# core.net
KiCad netlist of a schematic drawn in Altium Designer
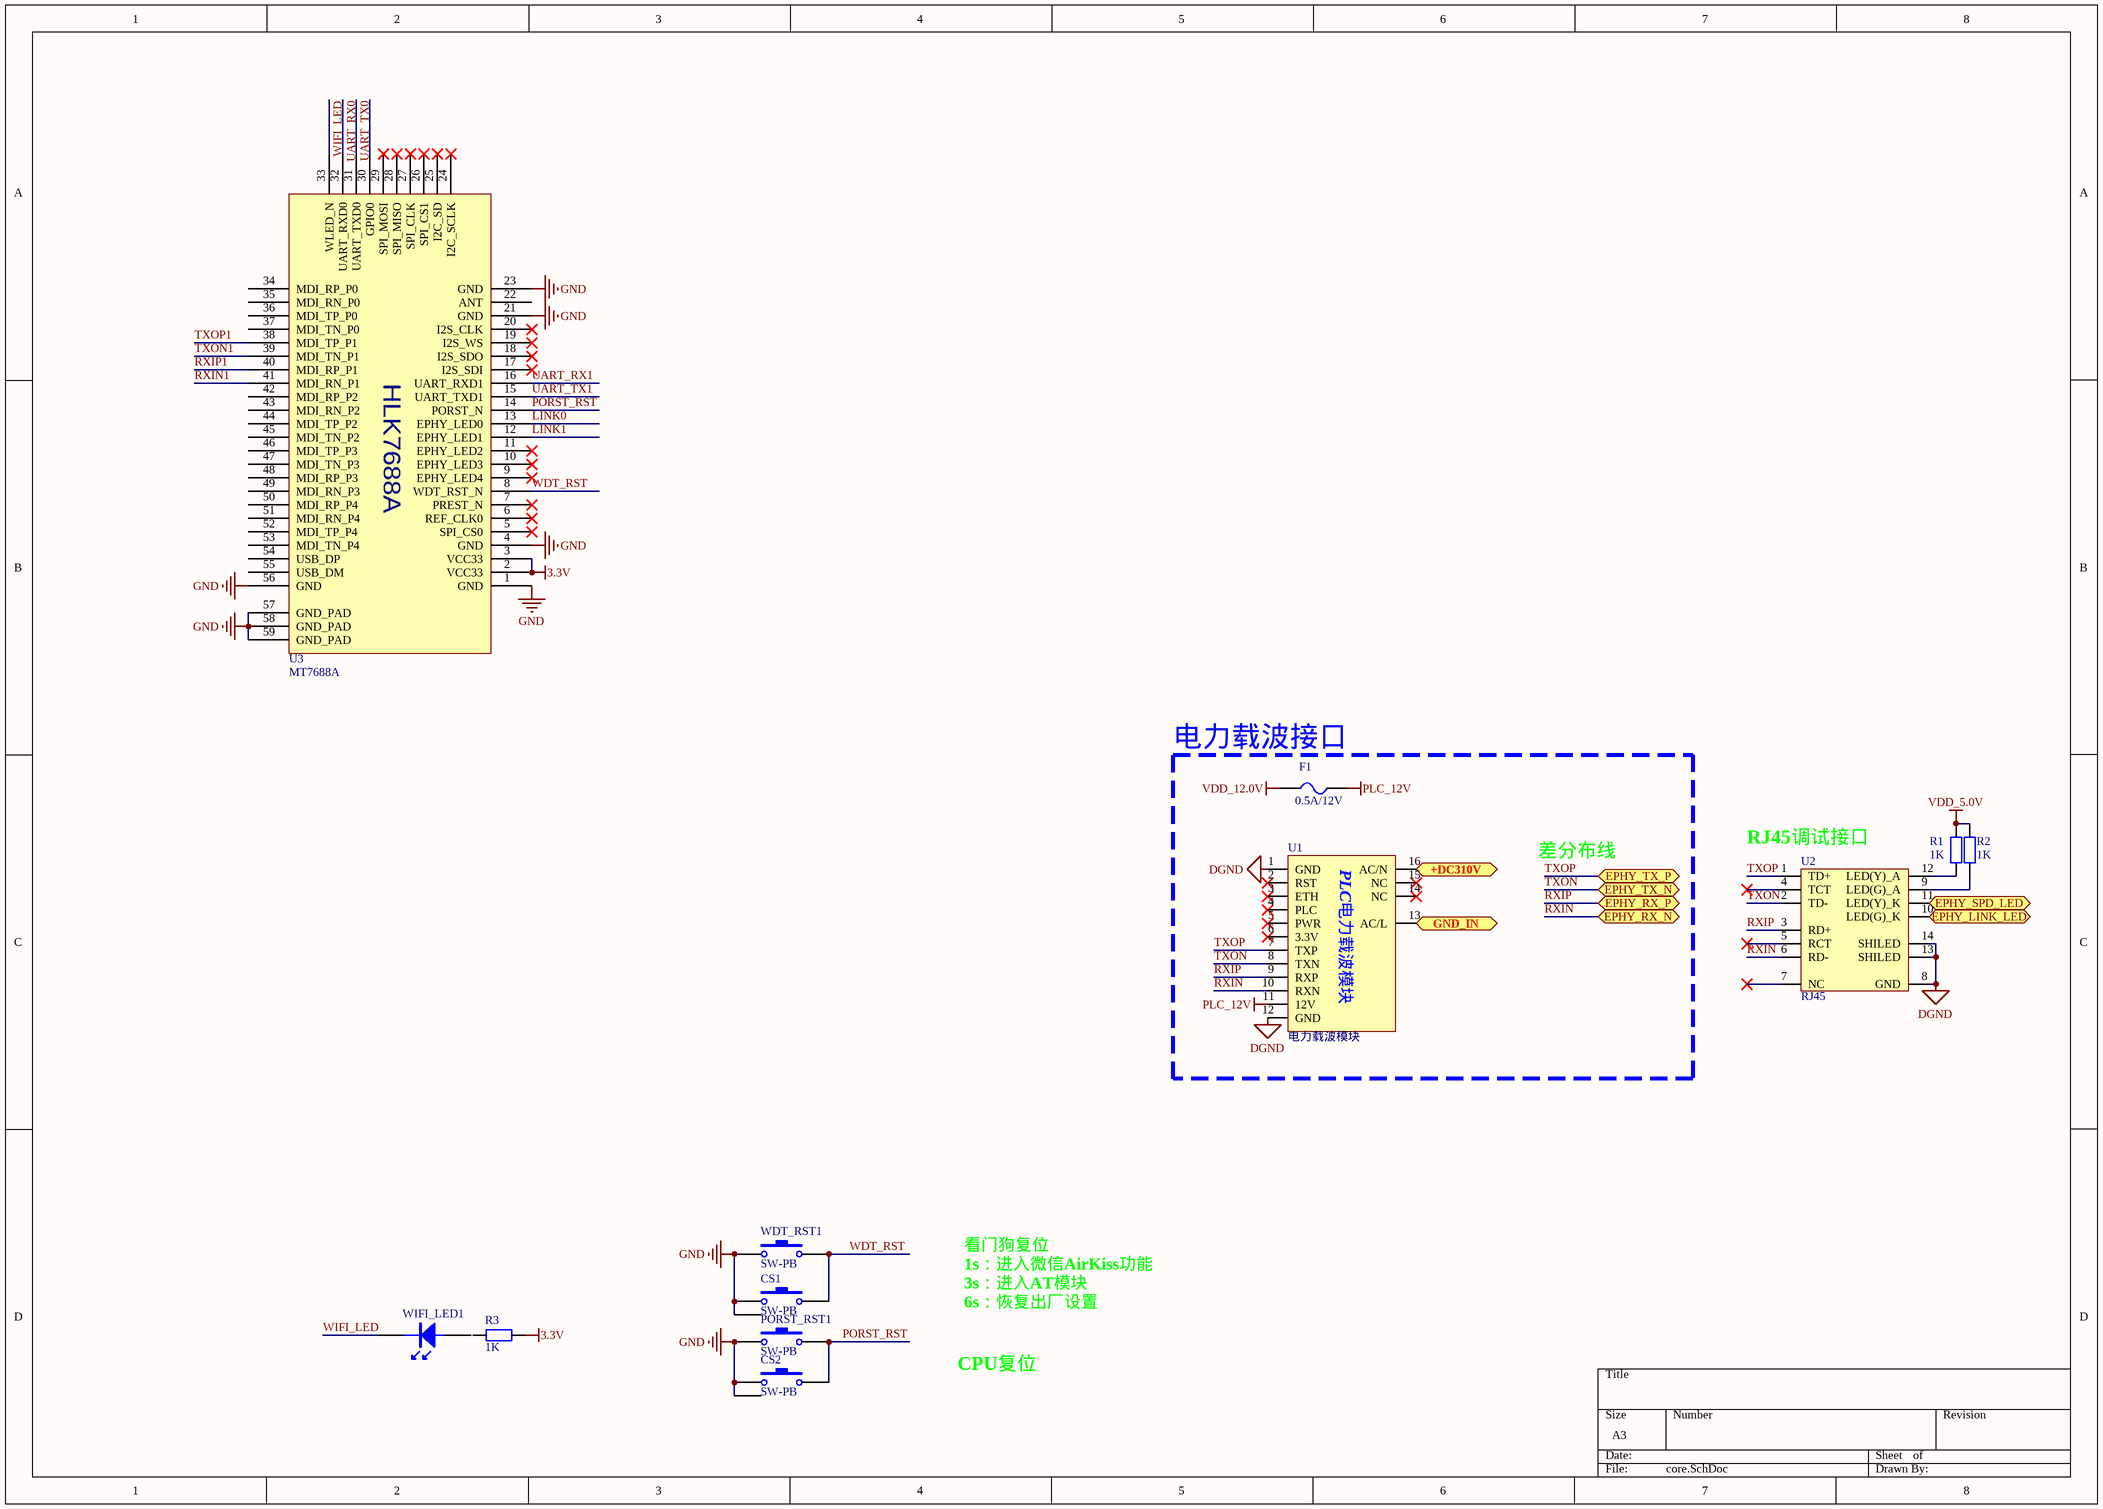
[diagram p0: core.SchDoc]

(export (version "E")
  (design (tool "Eeschema 10.0.6"))
  (components
    (comp (ref "CS1")
      (value "SW-PB")
      (footprint "K5")
      (description "Switch")
      (fields (field (name "PUBLISHER") "Altium Limited"))
      (libsource (lib "Miscellaneous Devices") (part "SW-PB"))
    )
    (comp (ref "CS2")
      (value "SW-PB")
      (footprint "K5")
      (description "Switch")
      (fields (field (name "PUBLISHER") "Altium Limited"))
      (libsource (lib "Miscellaneous Devices") (part "SW-PB"))
    )
    (comp (ref "F1")
      (value "0.5A/12V")
      (footprint "1206F")
      (description "保险丝")
      (libsource (lib "集大电协1.5") (part "Fuse"))
    )
    (comp (ref "PORST_RST1")
      (value "SW-PB")
      (footprint "SWITCH")
      (description "Switch")
      (fields (field (name "PUBLISHER") "Altium Limited"))
      (libsource (lib "") (part "SW-PB_1"))
    )
    (comp (ref "R1")
      (value "1K")
      (footprint "0805R")
      (description "电阻")
      (libsource (lib "集大电协1.5") (part "Res"))
    )
    (comp (ref "R2")
      (value "1K")
      (footprint "0805R")
      (description "电阻")
      (libsource (lib "集大电协1.5") (part "Res"))
    )
    (comp (ref "R3")
      (value "1K")
      (footprint "0805R")
      (description "电阻")
      (libsource (lib "Mylib") (part "Res"))
    )
    (comp (ref "U1")
      (value "电力载波模块")
      (footprint "电力载波模块6410（贴片排母）")
      (libsource (lib "集大电协1.5") (part "电力载波模块6410"))
    )
    (comp (ref "U2") (value "RJ45") (footprint "RJ45") (libsource (lib "集大电协1.5") (part "RJ45")))
    (comp (ref "U3")
      (value "MT7688A")
      (footprint "MT7688A")
      (description "MT7688A模组")
      (libsource (lib "Mylib") (part "MT7688A"))
    )
    (comp (ref "WDT_RST1")
      (value "SW-PB")
      (footprint "SWITCH")
      (description "Switch")
      (fields (field (name "PUBLISHER") "Altium Limited"))
      (libsource (lib "") (part "SW-PB_1"))
    )
    (comp (ref "WIFI_LED1")
      (value "~")
      (footprint "0603LED")
      (libsource (lib "Miscellaneous Devices") (part "LED"))
    )
  )
  (nets
    (net (code "1") (name "/+DC310V") (class "Default")
      (node (ref "U1") (pin "16") (pinfunction "AC/N_16") (pintype "passive"))
    )
    (net (code "2") (name "/EPHY_LINK_LED") (class "Default")
      (node (ref "U2") (pin "10") (pinfunction "LED(G)_K_10") (pintype "passive"))
    )
    (net (code "3") (name "/EPHY_SPD_LED") (class "Default")
      (node (ref "U2") (pin "11") (pinfunction "LED(Y)_K_11") (pintype "passive"))
    )
    (net (code "4") (name "/GND_IN") (class "Default")
      (node (ref "U1") (pin "13") (pinfunction "AC/L_13") (pintype "passive"))
    )
    (net (code "5") (name "/LINK0") (class "Default")
      (node (ref "U3") (pin "13") (pinfunction "EPHY_LED0_13") (pintype "passive"))
    )
    (net (code "6") (name "/LINK1") (class "Default")
      (node (ref "U3") (pin "12") (pinfunction "EPHY_LED1_12") (pintype "passive"))
    )
    (net (code "7") (name "/PORST_RST") (class "Default")
      (node (ref "CS2") (pin "2") (pinfunction "2_2") (pintype "passive"))
      (node (ref "PORST_RST1") (pin "2") (pinfunction "2_2") (pintype "passive"))
      (node (ref "U3") (pin "14") (pinfunction "PORST_N_14") (pintype "passive"))
    )
    (net (code "8") (name "/RXIN") (class "Default")
      (node (ref "U1") (pin "10") (pinfunction "RXN_10") (pintype "passive"))
      (node (ref "U2") (pin "6") (pinfunction "RD-_6") (pintype "passive"))
    )
    (net (code "9") (name "/RXIN1") (class "Default")
      (node (ref "U3") (pin "41") (pinfunction "MDI_RN_P1_41") (pintype "passive"))
    )
    (net (code "10") (name "/RXIP") (class "Default")
      (node (ref "U1") (pin "9") (pinfunction "RXP_9") (pintype "passive"))
      (node (ref "U2") (pin "3") (pinfunction "RD+_3") (pintype "passive"))
    )
    (net (code "11") (name "/RXIP1") (class "Default")
      (node (ref "U3") (pin "40") (pinfunction "MDI_RP_P1_40") (pintype "passive"))
    )
    (net (code "12") (name "/TXON") (class "Default")
      (node (ref "U1") (pin "8") (pinfunction "TXN_8") (pintype "passive"))
      (node (ref "U2") (pin "2") (pinfunction "TD-_2") (pintype "passive"))
    )
    (net (code "13") (name "/TXON1") (class "Default")
      (node (ref "U3") (pin "39") (pinfunction "MDI_TN_P1_39") (pintype "passive"))
    )
    (net (code "14") (name "/TXOP") (class "Default")
      (node (ref "U1") (pin "7") (pinfunction "TXP_7") (pintype "passive"))
      (node (ref "U2") (pin "1") (pinfunction "TD+_1") (pintype "passive"))
    )
    (net (code "15") (name "/TXOP1") (class "Default")
      (node (ref "U3") (pin "38") (pinfunction "MDI_TP_P1_38") (pintype "passive"))
    )
    (net (code "16") (name "/UART_RX0") (class "Default")
      (node (ref "U3") (pin "32") (pinfunction "UART_RXD0_32") (pintype "passive"))
    )
    (net (code "17") (name "/UART_RX1") (class "Default")
      (node (ref "U3") (pin "16") (pinfunction "UART_RXD1_16") (pintype "passive"))
    )
    (net (code "18") (name "/UART_TX0") (class "Default")
      (node (ref "U3") (pin "31") (pinfunction "UART_TXD0_31") (pintype "passive"))
    )
    (net (code "19") (name "/UART_TX1") (class "Default")
      (node (ref "U3") (pin "15") (pinfunction "UART_TXD1_15") (pintype "passive"))
    )
    (net (code "20") (name "/WDT_RST") (class "Default")
      (node (ref "CS1") (pin "2") (pinfunction "2_2") (pintype "passive"))
      (node (ref "U3") (pin "8") (pinfunction "WDT_RST_N_8") (pintype "passive"))
      (node (ref "WDT_RST1") (pin "2") (pinfunction "2_2") (pintype "passive"))
    )
    (net (code "21") (name "/WIFI_LED") (class "Default")
      (node (ref "U3") (pin "33") (pinfunction "WLED_N_33") (pintype "passive"))
      (node (ref "WIFI_LED1") (pin "2") (pinfunction "2_2") (pintype "passive"))
    )
    (net (code "22") (name "3.3V") (class "Default")
      (node (ref "R3") (pin "2") (pinfunction "2_2") (pintype "passive"))
      (node (ref "U3") (pin "2") (pinfunction "VCC33_2") (pintype "passive"))
      (node (ref "U3") (pin "3") (pinfunction "VCC33_3") (pintype "passive"))
    )
    (net (code "23") (name "DGND") (class "Default")
      (node (ref "U1") (pin "1") (pinfunction "GND_1") (pintype "passive"))
      (node (ref "U1") (pin "12") (pinfunction "GND_12") (pintype "passive"))
      (node (ref "U2") (pin "13") (pinfunction "SHILED_13") (pintype "passive"))
      (node (ref "U2") (pin "14") (pinfunction "SHILED_14") (pintype "passive"))
      (node (ref "U2") (pin "8") (pinfunction "GND_8") (pintype "passive"))
    )
    (net (code "24") (name "GND") (class "Default")
      (node (ref "CS1") (pin "1") (pinfunction "1_1") (pintype "passive"))
      (node (ref "CS1") (pin "3") (pintype "passive"))
      (node (ref "CS2") (pin "1") (pinfunction "1_1") (pintype "passive"))
      (node (ref "CS2") (pin "3") (pintype "passive"))
      (node (ref "PORST_RST1") (pin "1") (pinfunction "1_1") (pintype "passive"))
      (node (ref "U3") (pin "1") (pinfunction "GND_1") (pintype "passive"))
      (node (ref "U3") (pin "21") (pinfunction "GND_21") (pintype "passive"))
      (node (ref "U3") (pin "23") (pinfunction "GND_23") (pintype "passive"))
      (node (ref "U3") (pin "4") (pinfunction "GND_4") (pintype "passive"))
      (node (ref "U3") (pin "56") (pinfunction "GND_56") (pintype "passive"))
      (node (ref "U3") (pin "57") (pinfunction "GND_PAD_57") (pintype "passive"))
      (node (ref "U3") (pin "58") (pinfunction "GND_PAD_58") (pintype "passive"))
      (node (ref "U3") (pin "59") (pinfunction "GND_PAD_59") (pintype "passive"))
      (node (ref "WDT_RST1") (pin "1") (pinfunction "1_1") (pintype "passive"))
    )
    (net (code "25") (name "Net-(U2-LED(G)_A)") (class "Default")
      (node (ref "R2") (pin "2") (pinfunction "2_2") (pintype "passive"))
      (node (ref "U2") (pin "9") (pinfunction "LED(G)_A_9") (pintype "passive"))
    )
    (net (code "26") (name "Net-(U2-LED(Y)_A)") (class "Default")
      (node (ref "R1") (pin "2") (pinfunction "2_2") (pintype "passive"))
      (node (ref "U2") (pin "12") (pinfunction "LED(Y)_A_12") (pintype "passive"))
    )
    (net (code "27") (name "PLC_12V") (class "Default")
      (node (ref "F1") (pin "2") (pinfunction "2_2") (pintype "passive"))
      (node (ref "U1") (pin "11") (pinfunction "12V_11") (pintype "passive"))
    )
    (net (code "28") (name "VDD_5.0V") (class "Default")
      (node (ref "R1") (pin "1") (pinfunction "1_1") (pintype "passive"))
      (node (ref "R2") (pin "1") (pinfunction "1_1") (pintype "passive"))
    )
    (net (code "29") (name "VDD_12.0V") (class "Default")
      (node (ref "F1") (pin "1") (pinfunction "1_1") (pintype "passive"))
    )
    (net (code "30") (name "unconnected-(R3-Pad1)") (class "Default")
      (node (ref "R3") (pin "1") (pinfunction "1_1") (pintype "passive"))
    )
    (net (code "31") (name "unconnected-(U1-3.3V-Pad6)") (class "Default")
      (node (ref "U1") (pin "6") (pinfunction "3.3V_6") (pintype "passive+no_connect"))
    )
    (net (code "32") (name "unconnected-(U1-ETH-Pad3)") (class "Default")
      (node (ref "U1") (pin "3") (pinfunction "ETH_3") (pintype "passive+no_connect"))
    )
    (net (code "33") (name "unconnected-(U1-NC-Pad14)") (class "Default")
      (node (ref "U1") (pin "14") (pinfunction "NC_14") (pintype "passive+no_connect"))
    )
    (net (code "34") (name "unconnected-(U1-NC-Pad15)") (class "Default")
      (node (ref "U1") (pin "15") (pinfunction "NC_15") (pintype "passive+no_connect"))
    )
    (net (code "35") (name "unconnected-(U1-PLC-Pad4)") (class "Default")
      (node (ref "U1") (pin "4") (pinfunction "PLC_4") (pintype "passive+no_connect"))
    )
    (net (code "36") (name "unconnected-(U1-PWR-Pad5)") (class "Default")
      (node (ref "U1") (pin "5") (pinfunction "PWR_5") (pintype "passive+no_connect"))
    )
    (net (code "37") (name "unconnected-(U1-RST-Pad2)") (class "Default")
      (node (ref "U1") (pin "2") (pinfunction "RST_2") (pintype "passive+no_connect"))
    )
    (net (code "38") (name "unconnected-(U2-NC-Pad7)") (class "Default")
      (node (ref "U2") (pin "7") (pinfunction "NC_7") (pintype "passive+no_connect"))
    )
    (net (code "39") (name "unconnected-(U2-RCT-Pad5)") (class "Default")
      (node (ref "U2") (pin "5") (pinfunction "RCT_5") (pintype "passive+no_connect"))
    )
    (net (code "40") (name "unconnected-(U2-TCT-Pad4)") (class "Default")
      (node (ref "U2") (pin "4") (pinfunction "TCT_4") (pintype "passive+no_connect"))
    )
    (net (code "41") (name "unconnected-(U3-ANT-Pad22)") (class "Default")
      (node (ref "U3") (pin "22") (pinfunction "ANT_22") (pintype "passive"))
    )
    (net (code "42") (name "unconnected-(U3-EPHY_LED2-Pad11)") (class "Default")
      (node (ref "U3") (pin "11") (pinfunction "EPHY_LED2_11") (pintype "passive+no_connect"))
    )
    (net (code "43") (name "unconnected-(U3-EPHY_LED3-Pad10)") (class "Default")
      (node (ref "U3") (pin "10") (pinfunction "EPHY_LED3_10") (pintype "passive+no_connect"))
    )
    (net (code "44") (name "unconnected-(U3-EPHY_LED4-Pad9)") (class "Default")
      (node (ref "U3") (pin "9") (pinfunction "EPHY_LED4_9") (pintype "passive+no_connect"))
    )
    (net (code "45") (name "unconnected-(U3-GPIO0-Pad30)") (class "Default")
      (node (ref "U3") (pin "30") (pinfunction "GPIO0_30") (pintype "passive"))
    )
    (net (code "46") (name "unconnected-(U3-I2C_SCLK-Pad24)") (class "Default")
      (node (ref "U3") (pin "24") (pinfunction "I2C_SCLK_24") (pintype "passive+no_connect"))
    )
    (net (code "47") (name "unconnected-(U3-I2C_SD-Pad25)") (class "Default")
      (node (ref "U3") (pin "25") (pinfunction "I2C_SD_25") (pintype "passive+no_connect"))
    )
    (net (code "48") (name "unconnected-(U3-I2S_CLK-Pad20)") (class "Default")
      (node (ref "U3") (pin "20") (pinfunction "I2S_CLK_20") (pintype "passive+no_connect"))
    )
    (net (code "49") (name "unconnected-(U3-I2S_SDI-Pad17)") (class "Default")
      (node (ref "U3") (pin "17") (pinfunction "I2S_SDI_17") (pintype "passive+no_connect"))
    )
    (net (code "50") (name "unconnected-(U3-I2S_SDO-Pad18)") (class "Default")
      (node (ref "U3") (pin "18") (pinfunction "I2S_SDO_18") (pintype "passive+no_connect"))
    )
    (net (code "51") (name "unconnected-(U3-I2S_WS-Pad19)") (class "Default")
      (node (ref "U3") (pin "19") (pinfunction "I2S_WS_19") (pintype "passive+no_connect"))
    )
    (net (code "52") (name "unconnected-(U3-MDI_RN_P0-Pad35)") (class "Default")
      (node (ref "U3") (pin "35") (pinfunction "MDI_RN_P0_35") (pintype "passive"))
    )
    (net (code "53") (name "unconnected-(U3-MDI_RN_P2-Pad43)") (class "Default")
      (node (ref "U3") (pin "43") (pinfunction "MDI_RN_P2_43") (pintype "passive"))
    )
    (net (code "54") (name "unconnected-(U3-MDI_RN_P3-Pad49)") (class "Default")
      (node (ref "U3") (pin "49") (pinfunction "MDI_RN_P3_49") (pintype "passive"))
    )
    (net (code "55") (name "unconnected-(U3-MDI_RN_P4-Pad51)") (class "Default")
      (node (ref "U3") (pin "51") (pinfunction "MDI_RN_P4_51") (pintype "passive"))
    )
    (net (code "56") (name "unconnected-(U3-MDI_RP_P0-Pad34)") (class "Default")
      (node (ref "U3") (pin "34") (pinfunction "MDI_RP_P0_34") (pintype "passive"))
    )
    (net (code "57") (name "unconnected-(U3-MDI_RP_P2-Pad42)") (class "Default")
      (node (ref "U3") (pin "42") (pinfunction "MDI_RP_P2_42") (pintype "passive"))
    )
    (net (code "58") (name "unconnected-(U3-MDI_RP_P3-Pad48)") (class "Default")
      (node (ref "U3") (pin "48") (pinfunction "MDI_RP_P3_48") (pintype "passive"))
    )
    (net (code "59") (name "unconnected-(U3-MDI_RP_P4-Pad50)") (class "Default")
      (node (ref "U3") (pin "50") (pinfunction "MDI_RP_P4_50") (pintype "passive"))
    )
    (net (code "60") (name "unconnected-(U3-MDI_TN_P0-Pad37)") (class "Default")
      (node (ref "U3") (pin "37") (pinfunction "MDI_TN_P0_37") (pintype "passive"))
    )
    (net (code "61") (name "unconnected-(U3-MDI_TN_P2-Pad45)") (class "Default")
      (node (ref "U3") (pin "45") (pinfunction "MDI_TN_P2_45") (pintype "passive"))
    )
    (net (code "62") (name "unconnected-(U3-MDI_TN_P3-Pad47)") (class "Default")
      (node (ref "U3") (pin "47") (pinfunction "MDI_TN_P3_47") (pintype "passive"))
    )
    (net (code "63") (name "unconnected-(U3-MDI_TN_P4-Pad53)") (class "Default")
      (node (ref "U3") (pin "53") (pinfunction "MDI_TN_P4_53") (pintype "passive"))
    )
    (net (code "64") (name "unconnected-(U3-MDI_TP_P0-Pad36)") (class "Default")
      (node (ref "U3") (pin "36") (pinfunction "MDI_TP_P0_36") (pintype "passive"))
    )
    (net (code "65") (name "unconnected-(U3-MDI_TP_P2-Pad44)") (class "Default")
      (node (ref "U3") (pin "44") (pinfunction "MDI_TP_P2_44") (pintype "passive"))
    )
    (net (code "66") (name "unconnected-(U3-MDI_TP_P3-Pad46)") (class "Default")
      (node (ref "U3") (pin "46") (pinfunction "MDI_TP_P3_46") (pintype "passive"))
    )
    (net (code "67") (name "unconnected-(U3-MDI_TP_P4-Pad52)") (class "Default")
      (node (ref "U3") (pin "52") (pinfunction "MDI_TP_P4_52") (pintype "passive"))
    )
    (net (code "68") (name "unconnected-(U3-PREST_N-Pad7)") (class "Default")
      (node (ref "U3") (pin "7") (pinfunction "PREST_N_7") (pintype "passive+no_connect"))
    )
    (net (code "69") (name "unconnected-(U3-REF_CLK0-Pad6)") (class "Default")
      (node (ref "U3") (pin "6") (pinfunction "REF_CLK0_6") (pintype "passive+no_connect"))
    )
    (net (code "70") (name "unconnected-(U3-SPI_CLK-Pad27)") (class "Default")
      (node (ref "U3") (pin "27") (pinfunction "SPI_CLK_27") (pintype "passive+no_connect"))
    )
    (net (code "71") (name "unconnected-(U3-SPI_CS0-Pad5)") (class "Default")
      (node (ref "U3") (pin "5") (pinfunction "SPI_CS0_5") (pintype "passive+no_connect"))
    )
    (net (code "72") (name "unconnected-(U3-SPI_CS1-Pad26)") (class "Default")
      (node (ref "U3") (pin "26") (pinfunction "SPI_CS1_26") (pintype "passive+no_connect"))
    )
    (net (code "73") (name "unconnected-(U3-SPI_MISO-Pad28)") (class "Default")
      (node (ref "U3") (pin "28") (pinfunction "SPI_MISO_28") (pintype "passive+no_connect"))
    )
    (net (code "74") (name "unconnected-(U3-SPI_MOSI-Pad29)") (class "Default")
      (node (ref "U3") (pin "29") (pinfunction "SPI_MOSI_29") (pintype "passive+no_connect"))
    )
    (net (code "75") (name "unconnected-(U3-USB_DM-Pad55)") (class "Default")
      (node (ref "U3") (pin "55") (pinfunction "USB_DM_55") (pintype "passive"))
    )
    (net (code "76") (name "unconnected-(U3-USB_DP-Pad54)") (class "Default")
      (node (ref "U3") (pin "54") (pinfunction "USB_DP_54") (pintype "passive"))
    )
    (net (code "77") (name "unconnected-(WIFI_LED1-Pad1)") (class "Default")
      (node (ref "WIFI_LED1") (pin "1") (pinfunction "1_1") (pintype "passive"))
    )
  )
)
